# CoreModule.net
KiCad netlist of a schematic drawn in Altium Designer
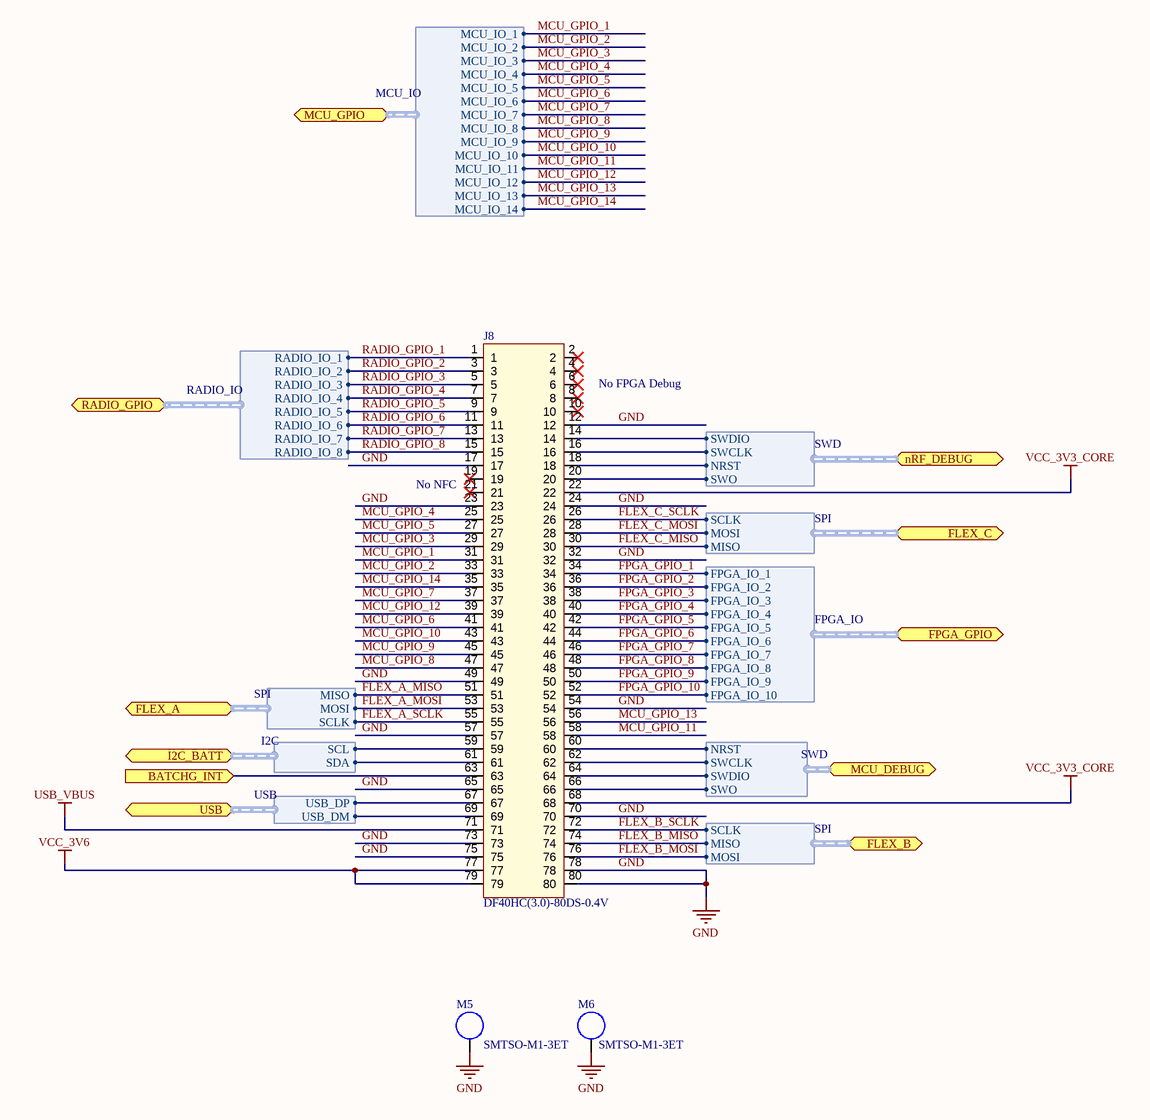
[diagram p0: CoreModule.SchDoc]

(export (version "E")
  (design (tool "Eeschema 10.0.6"))
  (components
    (comp (ref "J8")
      (value "DF40HC(3.0)-80DS-0.4V")
      (footprint "con80_hirose-df40c-80ds_129h")
      (description "CONN RCPT 80POS 0.4MM SMD GOLD 3.0MM")
      (fields (field (name "MFG") "Hirose") (field (name "VOLTAGE") "30V"))
      (libsource (lib "SynapseLibrary") (part "DF40C-80DS-0.4(51)"))
    )
    (comp (ref "M5")
      (value "SMTSO-M1-3ET")
      (footprint "standoff_hole2p50p")
      (description "SMT mounted PEM Standoff, M1, length 3mm")
      (fields (field (name "MFG") "Penn Engineering"))
      (libsource (lib "SynapseLibrary") (part "SMTSO-M1-3ET"))
    )
    (comp (ref "M6")
      (value "SMTSO-M1-3ET")
      (footprint "standoff_hole2p50p")
      (description "SMT mounted PEM Standoff, M1, length 3mm")
      (fields (field (name "MFG") "Penn Engineering"))
      (libsource (lib "SynapseLibrary") (part "SMTSO-M1-3ET"))
    )
  )
  (nets
    (net (code "8") (name "/BATCHG_INT") (class "Default")
      (node (ref "J8") (pin "63") (pinfunction "63_63") (pintype "passive"))
    )
    (net (code "9") (name "/FLEX_A_MISO") (class "Default")
      (node (ref "J8") (pin "51") (pinfunction "51_51") (pintype "passive"))
    )
    (net (code "10") (name "/FLEX_A_MOSI") (class "Default")
      (node (ref "J8") (pin "53") (pinfunction "53_53") (pintype "passive"))
    )
    (net (code "11") (name "/FLEX_A_SCLK") (class "Default")
      (node (ref "J8") (pin "55") (pinfunction "55_55") (pintype "passive"))
    )
    (net (code "12") (name "/FLEX_B_MISO") (class "Default")
      (node (ref "J8") (pin "74") (pinfunction "74_74") (pintype "passive"))
    )
    (net (code "13") (name "/FLEX_B_MOSI") (class "Default")
      (node (ref "J8") (pin "76") (pinfunction "76_76") (pintype "passive"))
    )
    (net (code "14") (name "/FLEX_B_SCLK") (class "Default")
      (node (ref "J8") (pin "72") (pinfunction "72_72") (pintype "passive"))
    )
    (net (code "15") (name "/FLEX_C_MISO") (class "Default")
      (node (ref "J8") (pin "30") (pinfunction "30_30") (pintype "passive"))
    )
    (net (code "16") (name "/FLEX_C_MOSI") (class "Default")
      (node (ref "J8") (pin "28") (pinfunction "28_28") (pintype "passive"))
    )
    (net (code "17") (name "/FLEX_C_SCLK") (class "Default")
      (node (ref "J8") (pin "26") (pinfunction "26_26") (pintype "passive"))
    )
    (net (code "18") (name "/FPGA_GPIO_1") (class "Default")
      (node (ref "J8") (pin "34") (pinfunction "34_34") (pintype "passive"))
    )
    (net (code "19") (name "/FPGA_GPIO_2") (class "Default")
      (node (ref "J8") (pin "36") (pinfunction "36_36") (pintype "passive"))
    )
    (net (code "20") (name "/FPGA_GPIO_3") (class "Default")
      (node (ref "J8") (pin "38") (pinfunction "38_38") (pintype "passive"))
    )
    (net (code "21") (name "/FPGA_GPIO_4") (class "Default")
      (node (ref "J8") (pin "40") (pinfunction "40_40") (pintype "passive"))
    )
    (net (code "22") (name "/FPGA_GPIO_5") (class "Default")
      (node (ref "J8") (pin "42") (pinfunction "42_42") (pintype "passive"))
    )
    (net (code "23") (name "/FPGA_GPIO_6") (class "Default")
      (node (ref "J8") (pin "44") (pinfunction "44_44") (pintype "passive"))
    )
    (net (code "24") (name "/FPGA_GPIO_7") (class "Default")
      (node (ref "J8") (pin "46") (pinfunction "46_46") (pintype "passive"))
    )
    (net (code "25") (name "/FPGA_GPIO_8") (class "Default")
      (node (ref "J8") (pin "48") (pinfunction "48_48") (pintype "passive"))
    )
    (net (code "26") (name "/FPGA_GPIO_9") (class "Default")
      (node (ref "J8") (pin "50") (pinfunction "50_50") (pintype "passive"))
    )
    (net (code "27") (name "/FPGA_GPIO_10") (class "Default")
      (node (ref "J8") (pin "52") (pinfunction "52_52") (pintype "passive"))
    )
    (net (code "28") (name "/MCU_GPIO_1") (class "Default")
      (node (ref "J8") (pin "31") (pinfunction "31_31") (pintype "passive"))
    )
    (net (code "29") (name "/MCU_GPIO_2") (class "Default")
      (node (ref "J8") (pin "33") (pinfunction "33_33") (pintype "passive"))
    )
    (net (code "30") (name "/MCU_GPIO_3") (class "Default")
      (node (ref "J8") (pin "29") (pinfunction "29_29") (pintype "passive"))
    )
    (net (code "31") (name "/MCU_GPIO_4") (class "Default")
      (node (ref "J8") (pin "25") (pinfunction "25_25") (pintype "passive"))
    )
    (net (code "32") (name "/MCU_GPIO_5") (class "Default")
      (node (ref "J8") (pin "27") (pinfunction "27_27") (pintype "passive"))
    )
    (net (code "33") (name "/MCU_GPIO_6") (class "Default")
      (node (ref "J8") (pin "41") (pinfunction "41_41") (pintype "passive"))
    )
    (net (code "34") (name "/MCU_GPIO_7") (class "Default")
      (node (ref "J8") (pin "37") (pinfunction "37_37") (pintype "passive"))
    )
    (net (code "35") (name "/MCU_GPIO_8") (class "Default")
      (node (ref "J8") (pin "47") (pinfunction "47_47") (pintype "passive"))
    )
    (net (code "36") (name "/MCU_GPIO_9") (class "Default")
      (node (ref "J8") (pin "45") (pinfunction "45_45") (pintype "passive"))
    )
    (net (code "37") (name "/MCU_GPIO_10") (class "Default")
      (node (ref "J8") (pin "43") (pinfunction "43_43") (pintype "passive"))
    )
    (net (code "38") (name "/MCU_GPIO_11") (class "Default")
      (node (ref "J8") (pin "58") (pinfunction "58_58") (pintype "passive"))
    )
    (net (code "39") (name "/MCU_GPIO_12") (class "Default")
      (node (ref "J8") (pin "39") (pinfunction "39_39") (pintype "passive"))
    )
    (net (code "40") (name "/MCU_GPIO_13") (class "Default")
      (node (ref "J8") (pin "56") (pinfunction "56_56") (pintype "passive"))
    )
    (net (code "41") (name "/MCU_GPIO_14") (class "Default")
      (node (ref "J8") (pin "35") (pinfunction "35_35") (pintype "passive"))
    )
    (net (code "42") (name "/RADIO_GPIO_1") (class "Default")
      (node (ref "J8") (pin "1") (pinfunction "1_1") (pintype "passive"))
    )
    (net (code "43") (name "/RADIO_GPIO_2") (class "Default")
      (node (ref "J8") (pin "3") (pinfunction "3_3") (pintype "passive"))
    )
    (net (code "44") (name "/RADIO_GPIO_3") (class "Default")
      (node (ref "J8") (pin "5") (pinfunction "5_5") (pintype "passive"))
    )
    (net (code "45") (name "/RADIO_GPIO_4") (class "Default")
      (node (ref "J8") (pin "7") (pinfunction "7_7") (pintype "passive"))
    )
    (net (code "46") (name "/RADIO_GPIO_5") (class "Default")
      (node (ref "J8") (pin "9") (pinfunction "9_9") (pintype "passive"))
    )
    (net (code "47") (name "/RADIO_GPIO_6") (class "Default")
      (node (ref "J8") (pin "11") (pinfunction "11_11") (pintype "passive"))
    )
    (net (code "48") (name "/RADIO_GPIO_7") (class "Default")
      (node (ref "J8") (pin "13") (pinfunction "13_13") (pintype "passive"))
    )
    (net (code "49") (name "/RADIO_GPIO_8") (class "Default")
      (node (ref "J8") (pin "15") (pinfunction "15_15") (pintype "passive"))
    )
    (net (code "50") (name "/SCL") (class "Default")
      (node (ref "J8") (pin "59") (pinfunction "59_59") (pintype "passive"))
    )
    (net (code "51") (name "/SDA") (class "Default")
      (node (ref "J8") (pin "61") (pinfunction "61_61") (pintype "passive"))
    )
    (net (code "52") (name "/USB_DM") (class "Default")
      (node (ref "J8") (pin "69") (pinfunction "69_69") (pintype "passive"))
    )
    (net (code "53") (name "/USB_DP") (class "Default")
      (node (ref "J8") (pin "67") (pinfunction "67_67") (pintype "passive"))
    )
    (net (code "61") (name "GND") (class "Default")
      (node (ref "J8") (pin "12") (pinfunction "12_12") (pintype "passive"))
      (node (ref "J8") (pin "17") (pinfunction "17_17") (pintype "passive"))
      (node (ref "J8") (pin "23") (pinfunction "23_23") (pintype "passive"))
      (node (ref "J8") (pin "24") (pinfunction "24_24") (pintype "passive"))
      (node (ref "J8") (pin "32") (pinfunction "32_32") (pintype "passive"))
      (node (ref "J8") (pin "49") (pinfunction "49_49") (pintype "passive"))
      (node (ref "J8") (pin "54") (pinfunction "54_54") (pintype "passive"))
      (node (ref "J8") (pin "57") (pinfunction "57_57") (pintype "passive"))
      (node (ref "J8") (pin "65") (pinfunction "65_65") (pintype "passive"))
      (node (ref "J8") (pin "70") (pinfunction "70_70") (pintype "passive"))
      (node (ref "J8") (pin "73") (pinfunction "73_73") (pintype "passive"))
      (node (ref "J8") (pin "75") (pinfunction "75_75") (pintype "passive"))
      (node (ref "J8") (pin "78") (pinfunction "78_78") (pintype "passive"))
      (node (ref "J8") (pin "80") (pinfunction "80_80") (pintype "passive"))
      (node (ref "M5") (pin "1") (pinfunction "1_1") (pintype "passive"))
      (node (ref "M6") (pin "1") (pinfunction "1_1") (pintype "passive"))
    )
    (net (code "62") (name "USB_VBUS") (class "Default")
      (node (ref "J8") (pin "71") (pinfunction "71_71") (pintype "passive"))
    )
    (net (code "63") (name "VCC_3V3_CORE") (class "Default")
      (node (ref "J8") (pin "22") (pinfunction "22_22") (pintype "passive"))
      (node (ref "J8") (pin "68") (pinfunction "68_68") (pintype "passive"))
    )
    (net (code "64") (name "VCC_3V6") (class "Default")
      (node (ref "J8") (pin "77") (pinfunction "77_77") (pintype "passive"))
      (node (ref "J8") (pin "79") (pinfunction "79_79") (pintype "passive"))
    )
    (net (code "65") (name "unconnected-(J8-Pad2)") (class "Default")
      (node (ref "J8") (pin "2") (pinfunction "2_2") (pintype "passive+no_connect"))
    )
    (net (code "66") (name "unconnected-(J8-Pad4)") (class "Default")
      (node (ref "J8") (pin "4") (pinfunction "4_4") (pintype "passive+no_connect"))
    )
    (net (code "67") (name "unconnected-(J8-Pad6)") (class "Default")
      (node (ref "J8") (pin "6") (pinfunction "6_6") (pintype "passive+no_connect"))
    )
    (net (code "68") (name "unconnected-(J8-Pad8)") (class "Default")
      (node (ref "J8") (pin "8") (pinfunction "8_8") (pintype "passive+no_connect"))
    )
    (net (code "69") (name "unconnected-(J8-Pad10)") (class "Default")
      (node (ref "J8") (pin "10") (pinfunction "10_10") (pintype "passive+no_connect"))
    )
    (net (code "70") (name "unconnected-(J8-Pad14)") (class "Default")
      (node (ref "J8") (pin "14") (pinfunction "14_14") (pintype "passive"))
    )
    (net (code "71") (name "unconnected-(J8-Pad16)") (class "Default")
      (node (ref "J8") (pin "16") (pinfunction "16_16") (pintype "passive"))
    )
    (net (code "72") (name "unconnected-(J8-Pad18)") (class "Default")
      (node (ref "J8") (pin "18") (pinfunction "18_18") (pintype "passive"))
    )
    (net (code "73") (name "unconnected-(J8-Pad19)") (class "Default")
      (node (ref "J8") (pin "19") (pinfunction "19_19") (pintype "passive+no_connect"))
    )
    (net (code "74") (name "unconnected-(J8-Pad20)") (class "Default")
      (node (ref "J8") (pin "20") (pinfunction "20_20") (pintype "passive"))
    )
    (net (code "75") (name "unconnected-(J8-Pad21)") (class "Default")
      (node (ref "J8") (pin "21") (pinfunction "21_21") (pintype "passive+no_connect"))
    )
    (net (code "76") (name "unconnected-(J8-Pad60)") (class "Default")
      (node (ref "J8") (pin "60") (pinfunction "60_60") (pintype "passive"))
    )
    (net (code "77") (name "unconnected-(J8-Pad62)") (class "Default")
      (node (ref "J8") (pin "62") (pinfunction "62_62") (pintype "passive"))
    )
    (net (code "78") (name "unconnected-(J8-Pad64)") (class "Default")
      (node (ref "J8") (pin "64") (pinfunction "64_64") (pintype "passive"))
    )
    (net (code "79") (name "unconnected-(J8-Pad66)") (class "Default")
      (node (ref "J8") (pin "66") (pinfunction "66_66") (pintype "passive"))
    )
  )
)
